# AVR_Programmer.net
KiCad netlist of a schematic drawn in Altium Designer
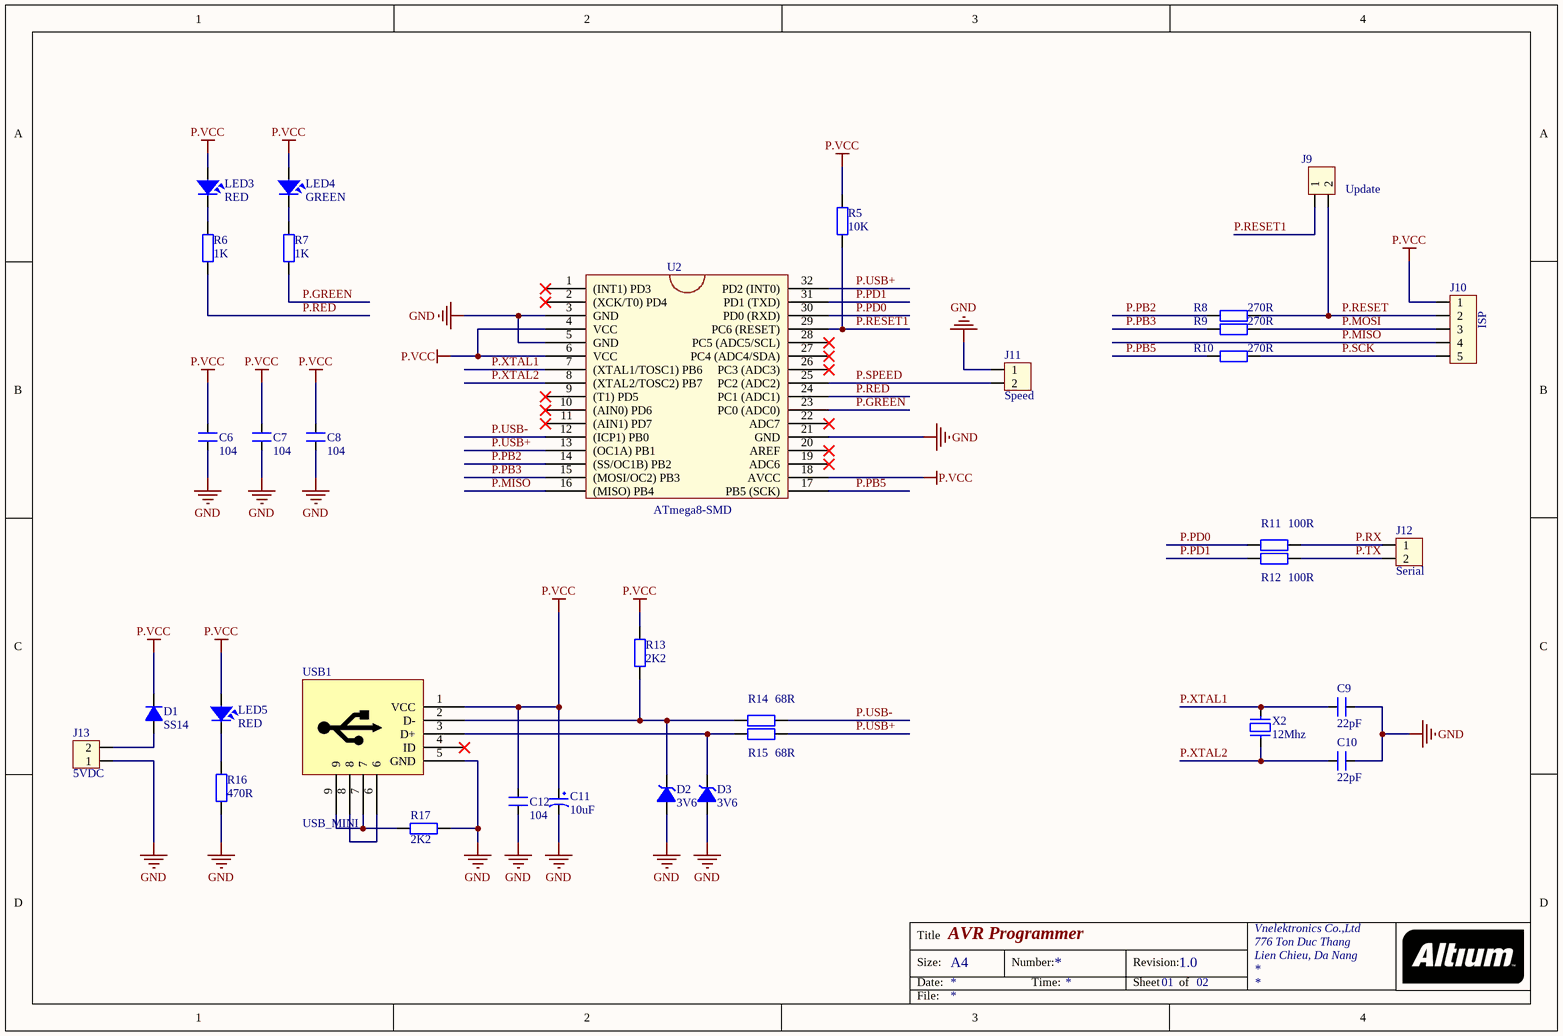
[diagram p0: AVR Programmer.SchDoc]

(export (version "E")
  (design (tool "Eeschema 10.0.6"))
  (components
    (comp (ref "C6")
      (value "104")
      (footprint "C0805")
      (description "Cap np 104 => 105pF")
      (libsource (lib "syhaunguyen") (part "CN2"))
    )
    (comp (ref "C7")
      (value "104")
      (footprint "C0805")
      (description "Cap np 104 => 105pF")
      (libsource (lib "syhaunguyen") (part "CN2"))
    )
    (comp (ref "C8")
      (value "104")
      (footprint "C0805")
      (description "Cap np 104 => 105pF")
      (libsource (lib "syhaunguyen") (part "CN2"))
    )
    (comp (ref "C9")
      (value "22pF")
      (footprint "C0603")
      (description "Cap np  1pF - 472pF")
      (libsource (lib "syhaunguyen") (part "CN1"))
    )
    (comp (ref "C10")
      (value "22pF")
      (footprint "C0603")
      (description "Cap np  1pF - 472pF")
      (libsource (lib "syhaunguyen") (part "CN1"))
    )
    (comp (ref "C11")
      (value "10uF")
      (footprint "C1210")
      (description "Cap P  0,1uF < 22uF , 16 - 50V")
      (libsource (lib "syhaunguyen") (part "CP1"))
    )
    (comp (ref "C12")
      (value "104")
      (footprint "C0805")
      (description "Cap np 104 => 105pF")
      (libsource (lib "syhaunguyen") (part "CN2"))
    )
    (comp (ref "D1")
      (value "SS14")
      (footprint "SS14")
      (description "Diode 1A")
      (libsource (lib "syhaunguyen") (part "D1A"))
    )
    (comp (ref "D2")
      (value "3V6")
      (footprint "1N5223")
      (description "Diode Zenner")
      (libsource (lib "syhaunguyen") (part "DZ"))
    )
    (comp (ref "D3")
      (value "3V6")
      (footprint "1N5223")
      (description "Diode Zenner")
      (libsource (lib "syhaunguyen") (part "DZ"))
    )
    (comp (ref "J9")
      (value "Update")
      (footprint "Header_2")
      (description "Header 2 (Green)")
      (libsource (lib "syhaunguyen") (part "Hed2"))
    )
    (comp (ref "J10")
      (value "ISP")
      (footprint "Header_5")
      (description "Header 5 (Green)")
      (libsource (lib "Tran Tuan") (part "Hed5"))
    )
    (comp (ref "J11")
      (value "Speed")
      (footprint "Header_2")
      (description "Header 2 (Green)")
      (libsource (lib "") (part "Hed2_2"))
    )
    (comp (ref "J12")
      (value "Serial")
      (footprint "Header_2")
      (description "Header 2 (Green)")
      (libsource (lib "") (part "Hed2_2"))
    )
    (comp (ref "J13")
      (value "5VDC")
      (footprint "Header_2")
      (description "Header 2 (Green)")
      (libsource (lib "") (part "Hed2_1"))
    )
    (comp (ref "LED3")
      (value "RED")
      (footprint "Led 0805R")
      (description "LED Single colour Green and Red")
      (libsource (lib "syhaunguyen") (part "LED"))
    )
    (comp (ref "LED4")
      (value "GREEN")
      (footprint "Led 0805G")
      (description "LED Single colour Green and Red")
      (libsource (lib "syhaunguyen") (part "LED"))
    )
    (comp (ref "LED5")
      (value "RED")
      (footprint "Led 0805G")
      (description "LED Single colour Green and Red")
      (libsource (lib "syhaunguyen") (part "LED"))
    )
    (comp (ref "R5")
      (value "10K")
      (footprint "RESC2012(0805)")
      (description "Resistor")
      (fields (field (name "Comment") "Res2") (field (name "PUBLISHER") "Altium Limited"))
      (libsource (lib "") (part "Res2_3"))
    )
    (comp (ref "R6")
      (value "1K")
      (footprint "RESC2012(0805)")
      (description "Resistor")
      (fields (field (name "Comment") "Res2") (field (name "PUBLISHER") "Altium Limited"))
      (libsource (lib "") (part "Res2_2"))
    )
    (comp (ref "R7")
      (value "1K")
      (footprint "RESC2012(0805)")
      (description "Resistor")
      (fields (field (name "Comment") "Res2") (field (name "PUBLISHER") "Altium Limited"))
      (libsource (lib "") (part "Res2_2"))
    )
    (comp (ref "R8")
      (value "270R")
      (footprint "RESC2012(0805)")
      (description "Resistor")
      (fields (field (name "Comment") "Res2") (field (name "PUBLISHER") "Altium Limited"))
      (libsource (lib "") (part "Res2_1"))
    )
    (comp (ref "R9")
      (value "270R")
      (footprint "RESC2012(0805)")
      (description "Resistor")
      (fields (field (name "Comment") "Res2") (field (name "PUBLISHER") "Altium Limited"))
      (libsource (lib "") (part "Res2_1"))
    )
    (comp (ref "R10")
      (value "270R")
      (footprint "RESC2012(0805)")
      (description "Resistor")
      (fields (field (name "Comment") "Res2") (field (name "PUBLISHER") "Altium Limited"))
      (libsource (lib "") (part "Res2_1"))
    )
    (comp (ref "R11")
      (value "100R")
      (footprint "RESC2012(0805)")
      (description "Resistor")
      (fields (field (name "Comment") "Res2") (field (name "PUBLISHER") "Altium Limited"))
      (libsource (lib "") (part "Res2_1"))
    )
    (comp (ref "R12")
      (value "100R")
      (footprint "RESC2012(0805)")
      (description "Resistor")
      (fields (field (name "Comment") "Res2") (field (name "PUBLISHER") "Altium Limited"))
      (libsource (lib "") (part "Res2_1"))
    )
    (comp (ref "R13")
      (value "2K2")
      (footprint "RESC2012(0805)")
      (description "Resistor")
      (fields (field (name "Comment") "Res2") (field (name "PUBLISHER") "Altium Limited"))
      (libsource (lib "") (part "Res2_2"))
    )
    (comp (ref "R14")
      (value "68R")
      (footprint "RESC2012(0805)")
      (description "Resistor")
      (fields (field (name "Comment") "Res2") (field (name "PUBLISHER") "Altium Limited"))
      (libsource (lib "Miscellaneous Devices") (part "Res2"))
    )
    (comp (ref "R15")
      (value "68R")
      (footprint "RESC2012(0805)")
      (description "Resistor")
      (fields (field (name "Comment") "Res2") (field (name "PUBLISHER") "Altium Limited"))
      (libsource (lib "Miscellaneous Devices") (part "Res2"))
    )
    (comp (ref "R16")
      (value "470R")
      (footprint "RESC2012(0805)")
      (description "Resistor")
      (fields (field (name "Comment") "Res2") (field (name "PUBLISHER") "Altium Limited"))
      (libsource (lib "") (part "Res2_2"))
    )
    (comp (ref "R17")
      (value "2K2")
      (footprint "RESC2012(0805)")
      (description "Resistor")
      (fields (field (name "Comment") "Res2") (field (name "PUBLISHER") "Altium Limited"))
      (libsource (lib "") (part "Res2_1"))
    )
    (comp (ref "U2")
      (value "ATmega8-SMD")
      (footprint "ATMEGA_8_SMD")
      (description "High-performance, Low-power Atmel  ®  AVR  ®   8-bit Microcontroller")
      (libsource (lib "AT8") (part "ATmega8_SMD_32pin"))
    )
    (comp (ref "USB1") (value "USB_MINI") (footprint "USBMNIB") (libsource (lib "lpson") (part "USB_MINI")))
    (comp (ref "X2")
      (value "12Mhz")
      (footprint "CRYSTAL")
      (description "Crystal For all Crystal 2pin.")
      (libsource (lib "syhaunguyen") (part "XT2"))
    )
  )
  (nets
    (net (code "1") (name "/P.GREEN") (class "Default")
      (node (ref "R7") (pin "2") (pinfunction "2_2") (pintype "passive"))
      (node (ref "U2") (pin "23") (pinfunction "PC0_(ADC0)_23") (pintype "passive"))
    )
    (net (code "2") (name "/P.MISO") (class "Default")
      (node (ref "J10") (pin "4") (pinfunction "4_4") (pintype "passive"))
      (node (ref "U2") (pin "16") (pinfunction "(MISO)_PB4_16") (pintype "passive"))
    )
    (net (code "3") (name "/P.MOSI") (class "Default")
      (node (ref "J10") (pin "3") (pinfunction "3_3") (pintype "passive"))
      (node (ref "R9") (pin "2") (pinfunction "2_2") (pintype "passive"))
    )
    (net (code "4") (name "/P.PB2") (class "Default")
      (node (ref "R8") (pin "1") (pinfunction "1_1") (pintype "passive"))
      (node (ref "U2") (pin "14") (pinfunction "(SS/OC1B)_PB2_14") (pintype "passive"))
    )
    (net (code "5") (name "/P.PB3") (class "Default")
      (node (ref "R9") (pin "1") (pinfunction "1_1") (pintype "passive"))
      (node (ref "U2") (pin "15") (pinfunction "(MOSI/OC2)_PB3_15") (pintype "passive"))
    )
    (net (code "6") (name "/P.PB5") (class "Default")
      (node (ref "R10") (pin "1") (pinfunction "1_1") (pintype "passive"))
      (node (ref "U2") (pin "17") (pinfunction "PB5_(SCK)_17") (pintype "passive"))
    )
    (net (code "7") (name "/P.PD0") (class "Default")
      (node (ref "R11") (pin "1") (pinfunction "1_1") (pintype "passive"))
      (node (ref "U2") (pin "30") (pinfunction "PD0_(RXD)_30") (pintype "passive"))
    )
    (net (code "8") (name "/P.PD1") (class "Default")
      (node (ref "R12") (pin "1") (pinfunction "1_1") (pintype "passive"))
      (node (ref "U2") (pin "31") (pinfunction "PD1_(TXD)_31") (pintype "passive"))
    )
    (net (code "9") (name "/P.RED") (class "Default")
      (node (ref "R6") (pin "2") (pinfunction "2_2") (pintype "passive"))
      (node (ref "U2") (pin "24") (pinfunction "PC1_(ADC1)_24") (pintype "passive"))
    )
    (net (code "10") (name "/P.RESET") (class "Default")
      (node (ref "J10") (pin "2") (pinfunction "2_2") (pintype "passive"))
      (node (ref "J9") (pin "2") (pinfunction "2_2") (pintype "passive"))
      (node (ref "R8") (pin "2") (pinfunction "2_2") (pintype "passive"))
    )
    (net (code "11") (name "/P.RESET1") (class "Default")
      (node (ref "J9") (pin "1") (pinfunction "1_1") (pintype "passive"))
      (node (ref "R5") (pin "1") (pinfunction "1_1") (pintype "passive"))
      (node (ref "U2") (pin "29") (pinfunction "PC6_(RESET)_29") (pintype "passive"))
    )
    (net (code "12") (name "/P.RX") (class "Default")
      (node (ref "J12") (pin "1") (pinfunction "1_1") (pintype "passive"))
      (node (ref "R11") (pin "2") (pinfunction "2_2") (pintype "passive"))
    )
    (net (code "13") (name "/P.SCK") (class "Default")
      (node (ref "J10") (pin "5") (pinfunction "5_5") (pintype "passive"))
      (node (ref "R10") (pin "2") (pinfunction "2_2") (pintype "passive"))
    )
    (net (code "14") (name "/P.SPEED") (class "Default")
      (node (ref "J11") (pin "2") (pinfunction "2_2") (pintype "passive"))
      (node (ref "U2") (pin "25") (pinfunction "PC2_(ADC2)_25") (pintype "passive"))
    )
    (net (code "15") (name "/P.TX") (class "Default")
      (node (ref "J12") (pin "2") (pinfunction "2_2") (pintype "passive"))
      (node (ref "R12") (pin "2") (pinfunction "2_2") (pintype "passive"))
    )
    (net (code "16") (name "/P.USB+") (class "Default")
      (node (ref "R15") (pin "1") (pinfunction "1_1") (pintype "passive"))
      (node (ref "U2") (pin "13") (pinfunction "(OC1A)_PB1_13") (pintype "passive"))
      (node (ref "U2") (pin "32") (pinfunction "PD2_(INT0)_32") (pintype "passive"))
    )
    (net (code "17") (name "/P.USB-") (class "Default")
      (node (ref "R14") (pin "1") (pinfunction "1_1") (pintype "passive"))
      (node (ref "U2") (pin "12") (pinfunction "(ICP1)_PB0_12") (pintype "passive"))
    )
    (net (code "18") (name "/P.XTAL1") (class "Default")
      (node (ref "C9") (pin "2") (pinfunction "2_2") (pintype "passive"))
      (node (ref "U2") (pin "7") (pinfunction "(XTAL1/TOSC1)_PB6_7") (pintype "passive"))
      (node (ref "X2") (pin "1") (pinfunction "1_1") (pintype "passive"))
    )
    (net (code "19") (name "/P.XTAL2") (class "Default")
      (node (ref "C10") (pin "2") (pinfunction "2_2") (pintype "passive"))
      (node (ref "U2") (pin "8") (pinfunction "(XTAL2/TOSC2)_PB7_8") (pintype "passive"))
      (node (ref "X2") (pin "2") (pinfunction "2_2") (pintype "passive"))
    )
    (net (code "20") (name "GND") (class "Default")
      (node (ref "C10") (pin "1") (pinfunction "1_1") (pintype "passive"))
      (node (ref "C11") (pin "2") (pinfunction "2_2") (pintype "passive"))
      (node (ref "C12") (pin "1") (pinfunction "1_1") (pintype "passive"))
      (node (ref "C6") (pin "1") (pinfunction "1_1") (pintype "passive"))
      (node (ref "C7") (pin "1") (pinfunction "1_1") (pintype "passive"))
      (node (ref "C8") (pin "1") (pinfunction "1_1") (pintype "passive"))
      (node (ref "C9") (pin "1") (pinfunction "1_1") (pintype "passive"))
      (node (ref "D2") (pin "1") (pinfunction "A_1") (pintype "passive"))
      (node (ref "D3") (pin "1") (pinfunction "A_1") (pintype "passive"))
      (node (ref "J11") (pin "1") (pinfunction "1_1") (pintype "passive"))
      (node (ref "J13") (pin "1") (pinfunction "1_1") (pintype "passive"))
      (node (ref "R16") (pin "2") (pinfunction "2_2") (pintype "passive"))
      (node (ref "R17") (pin "2") (pinfunction "2_2") (pintype "passive"))
      (node (ref "U2") (pin "21") (pinfunction "GND_21") (pintype "passive"))
      (node (ref "U2") (pin "3") (pinfunction "GND_3") (pintype "passive"))
      (node (ref "U2") (pin "5") (pinfunction "GND_5") (pintype "passive"))
      (node (ref "USB1") (pin "5") (pinfunction "GND_5") (pintype "passive"))
    )
    (net (code "21") (name "Net-(D1-A)") (class "Default")
      (node (ref "D1") (pin "1") (pinfunction "A_1") (pintype "passive"))
      (node (ref "J13") (pin "2") (pinfunction "2_2") (pintype "passive"))
    )
    (net (code "22") (name "Net-(D2-K)") (class "Default")
      (node (ref "D2") (pin "2") (pinfunction "K_2") (pintype "passive"))
      (node (ref "R13") (pin "2") (pinfunction "2_2") (pintype "passive"))
      (node (ref "R14") (pin "2") (pinfunction "2_2") (pintype "passive"))
      (node (ref "USB1") (pin "2") (pinfunction "D-_2") (pintype "passive"))
    )
    (net (code "23") (name "Net-(D3-K)") (class "Default")
      (node (ref "D3") (pin "2") (pinfunction "K_2") (pintype "passive"))
      (node (ref "R15") (pin "2") (pinfunction "2_2") (pintype "passive"))
      (node (ref "USB1") (pin "3") (pinfunction "D+_3") (pintype "passive"))
    )
    (net (code "24") (name "Net-(LED3-Pad2)") (class "Default")
      (node (ref "LED3") (pin "2") (pinfunction "2_2") (pintype "passive"))
      (node (ref "R6") (pin "1") (pinfunction "1_1") (pintype "passive"))
    )
    (net (code "25") (name "Net-(LED4-Pad2)") (class "Default")
      (node (ref "LED4") (pin "2") (pinfunction "2_2") (pintype "passive"))
      (node (ref "R7") (pin "1") (pinfunction "1_1") (pintype "passive"))
    )
    (net (code "26") (name "Net-(LED5-Pad2)") (class "Default")
      (node (ref "LED5") (pin "2") (pinfunction "2_2") (pintype "passive"))
      (node (ref "R16") (pin "1") (pinfunction "1_1") (pintype "passive"))
    )
    (net (code "27") (name "Net-(R17-Pad1)") (class "Default")
      (node (ref "R17") (pin "1") (pinfunction "1_1") (pintype "passive"))
      (node (ref "USB1") (pin "7") (pinfunction "7_7") (pintype "passive"))
      (node (ref "USB1") (pin "9") (pinfunction "9_9") (pintype "passive"))
    )
    (net (code "28") (name "Net-(USB1-Pad6)") (class "Default")
      (node (ref "USB1") (pin "6") (pinfunction "6_6") (pintype "passive"))
      (node (ref "USB1") (pin "8") (pinfunction "8_8") (pintype "passive"))
    )
    (net (code "29") (name "P.VCC") (class "Default")
      (node (ref "C11") (pin "1") (pinfunction "1_1") (pintype "passive"))
      (node (ref "C12") (pin "2") (pinfunction "2_2") (pintype "passive"))
      (node (ref "C6") (pin "2") (pinfunction "2_2") (pintype "passive"))
      (node (ref "C7") (pin "2") (pinfunction "2_2") (pintype "passive"))
      (node (ref "C8") (pin "2") (pinfunction "2_2") (pintype "passive"))
      (node (ref "D1") (pin "2") (pinfunction "K_2") (pintype "passive"))
      (node (ref "J10") (pin "1") (pinfunction "1_1") (pintype "passive"))
      (node (ref "LED3") (pin "1") (pinfunction "1_1") (pintype "passive"))
      (node (ref "LED4") (pin "1") (pinfunction "1_1") (pintype "passive"))
      (node (ref "LED5") (pin "1") (pinfunction "1_1") (pintype "passive"))
      (node (ref "R13") (pin "1") (pinfunction "1_1") (pintype "passive"))
      (node (ref "R5") (pin "2") (pinfunction "2_2") (pintype "passive"))
      (node (ref "U2") (pin "18") (pinfunction "AVCC_18") (pintype "passive"))
      (node (ref "U2") (pin "4") (pinfunction "VCC_4") (pintype "passive"))
      (node (ref "U2") (pin "6") (pinfunction "VCC_6") (pintype "passive"))
      (node (ref "USB1") (pin "1") (pinfunction "VCC_1") (pintype "passive"))
    )
    (net (code "30") (name "unconnected-(U2-(AIN0)_PD6-Pad10)") (class "Default")
      (node (ref "U2") (pin "10") (pinfunction "(AIN0)_PD6_10") (pintype "passive+no_connect"))
    )
    (net (code "31") (name "unconnected-(U2-(AIN1)_PD7-Pad11)") (class "Default")
      (node (ref "U2") (pin "11") (pinfunction "(AIN1)_PD7_11") (pintype "passive+no_connect"))
    )
    (net (code "32") (name "unconnected-(U2-(INT1)_PD3-Pad1)") (class "Default")
      (node (ref "U2") (pin "1") (pinfunction "(INT1)_PD3_1") (pintype "passive+no_connect"))
    )
    (net (code "33") (name "unconnected-(U2-(T1)_PD5-Pad9)") (class "Default")
      (node (ref "U2") (pin "9") (pinfunction "(T1)_PD5_9") (pintype "passive+no_connect"))
    )
    (net (code "34") (name "unconnected-(U2-(XCK{slash}T0)_PD4-Pad2)") (class "Default")
      (node (ref "U2") (pin "2") (pinfunction "(XCK/T0)_PD4_2") (pintype "passive+no_connect"))
    )
    (net (code "35") (name "unconnected-(U2-ADC6-Pad19)") (class "Default")
      (node (ref "U2") (pin "19") (pinfunction "ADC6_19") (pintype "passive+no_connect"))
    )
    (net (code "36") (name "unconnected-(U2-ADC7-Pad22)") (class "Default")
      (node (ref "U2") (pin "22") (pinfunction "ADC7_22") (pintype "passive+no_connect"))
    )
    (net (code "37") (name "unconnected-(U2-AREF-Pad20)") (class "Default")
      (node (ref "U2") (pin "20") (pinfunction "AREF_20") (pintype "passive+no_connect"))
    )
    (net (code "38") (name "unconnected-(U2-PC3_(ADC3)-Pad26)") (class "Default")
      (node (ref "U2") (pin "26") (pinfunction "PC3_(ADC3)_26") (pintype "passive+no_connect"))
    )
    (net (code "39") (name "unconnected-(U2-PC4_(ADC4{slash}SDA)-Pad27)") (class "Default")
      (node (ref "U2") (pin "27") (pinfunction "PC4_(ADC4/SDA)_27") (pintype "passive+no_connect"))
    )
    (net (code "40") (name "unconnected-(U2-PC5_(ADC5{slash}SCL)-Pad28)") (class "Default")
      (node (ref "U2") (pin "28") (pinfunction "PC5_(ADC5/SCL)_28") (pintype "passive+no_connect"))
    )
    (net (code "41") (name "unconnected-(USB1-ID-Pad4)") (class "Default")
      (node (ref "USB1") (pin "4") (pinfunction "ID_4") (pintype "passive+no_connect"))
    )
  )
)
